# Wifi.net
KiCad netlist of a schematic drawn in Altium Designer
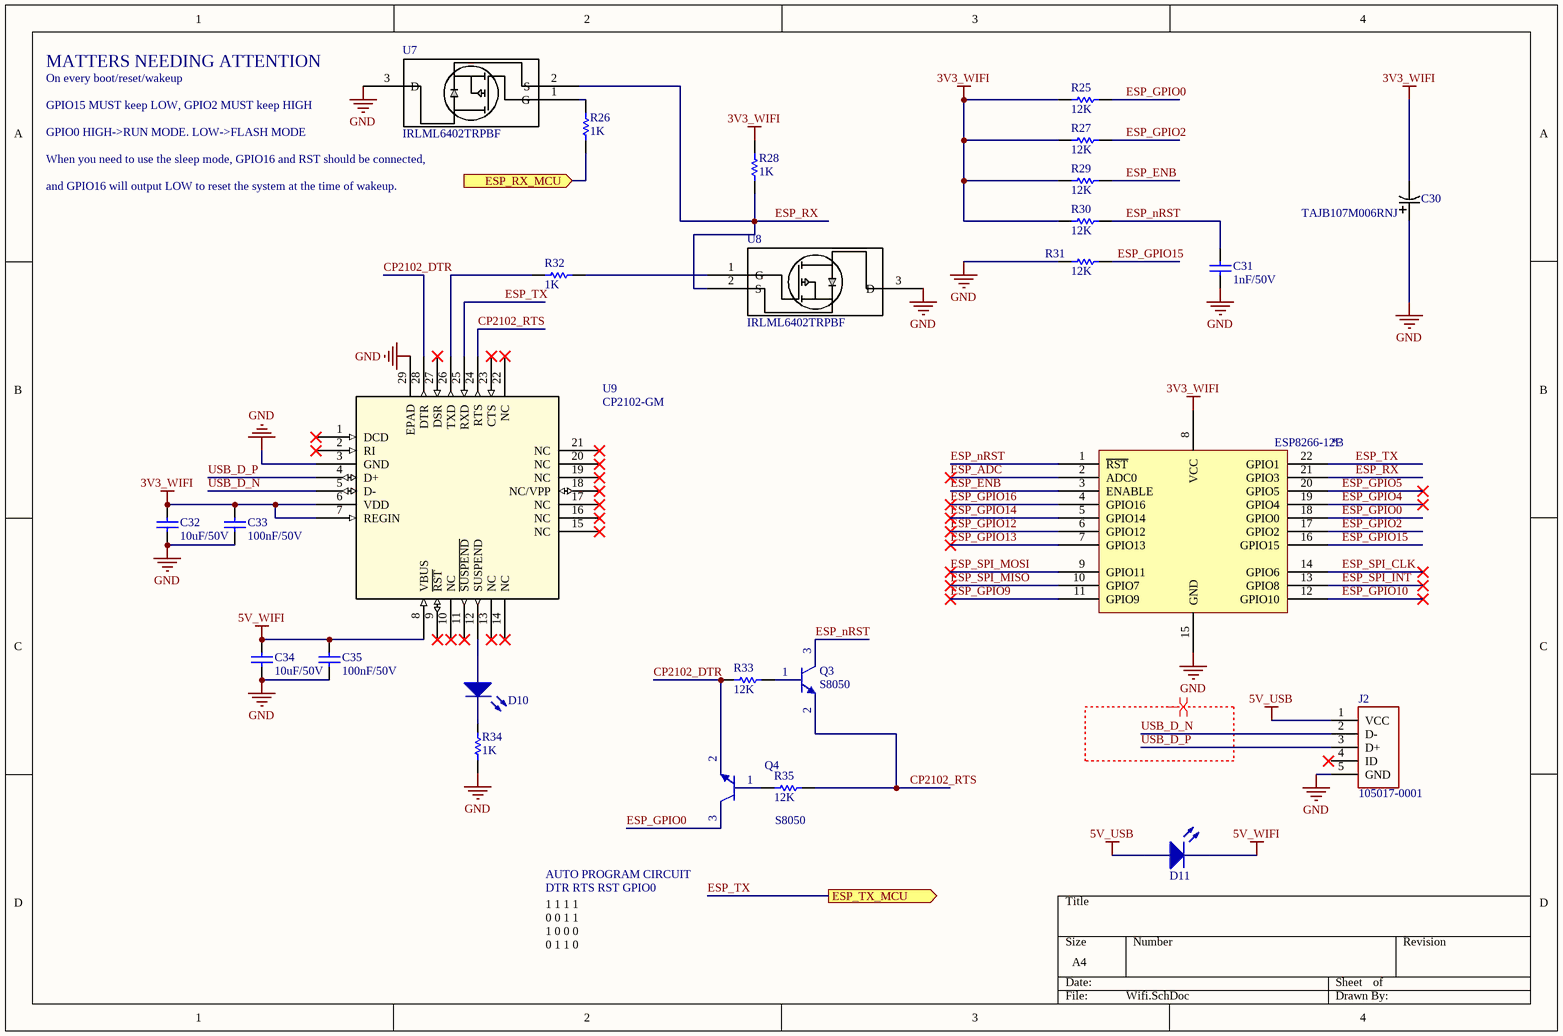
[diagram p0: Wifi.SchDoc]

(export (version "E")
  (design (tool "Eeschema 10.0.6"))
  (components
    (comp (ref "*3")
      (value "ESP8266-12F")
      (footprint "ESP8266")
      (libsource (lib "Schlib1") (part "ESP8266-12F"))
    )
    (comp (ref "C30")
      (value "TAJB107M006RNJ")
      (footprint "TAJB107M006RNJ")
      (fields (field (name "COPYRIGHT") "Copyright (C) 2018 Accelerated Designs. All rights reserved"))
      (libsource (lib "Integrated_Library") (part "TAJB107M006RNJ"))
    )
    (comp (ref "C31")
      (value "1nF/50V")
      (footprint "CAP-SM-0805")
      (description "CAP CER 1000PF 100V X7R 0805")
      (fields
        (field (name "MANUFACTURER") "Johanson Dielectrics Inc.")
        (field (name "MANUFACTURER PART NUMBER") "101X15W102MV4E")
      )
      (libsource (lib "Capacitor") (part "Cap-1nF-50V-0805"))
    )
    (comp (ref "C32")
      (value "10uF/50V")
      (footprint "CAP-SM-0805")
      (description "CAP CER 1000PF 100V X7R 0805")
      (fields
        (field (name "MANUFACTURER") "Johanson Dielectrics Inc.")
        (field (name "MANUFACTURER PART NUMBER") "101X15W102MV4E")
      )
      (libsource (lib "Capacitor") (part "Cap-1nF-50V-0805"))
    )
    (comp (ref "C33")
      (value "100nF/50V")
      (footprint "CAP-SM-0805")
      (description "CAP CER 1000PF 100V X7R 0805")
      (fields
        (field (name "MANUFACTURER") "Johanson Dielectrics Inc.")
        (field (name "MANUFACTURER PART NUMBER") "101X15W102MV4E")
      )
      (libsource (lib "Capacitor") (part "Cap-1nF-50V-0805"))
    )
    (comp (ref "C34")
      (value "10uF/50V")
      (footprint "CAP-SM-0805")
      (description "CAP CER 1000PF 100V X7R 0805")
      (fields
        (field (name "MANUFACTURER") "Johanson Dielectrics Inc.")
        (field (name "MANUFACTURER PART NUMBER") "101X15W102MV4E")
      )
      (libsource (lib "Capacitor") (part "Cap-1nF-50V-0805"))
    )
    (comp (ref "C35")
      (value "100nF/50V")
      (footprint "CAP-SM-0805")
      (description "CAP CER 1000PF 100V X7R 0805")
      (fields
        (field (name "MANUFACTURER") "Johanson Dielectrics Inc.")
        (field (name "MANUFACTURER PART NUMBER") "101X15W102MV4E")
      )
      (libsource (lib "Capacitor") (part "Cap-1nF-50V-0805"))
    )
    (comp (ref "D10") (value "LED") (footprint "LED_0603_Blue") (libsource (lib "PIF_C16_lib") (part "LED")))
    (comp (ref "D11") (value "LED") (footprint "LED_0603_Blue") (libsource (lib "PIF_C16_lib") (part "LED")))
    (comp (ref "J2")
      (value "105017-0001")
      (footprint "CONN_105017-0001")
      (description "No Description Available")
      (fields (field (name "COPYRIGHT") "Copyright (C) 2018 Accelerated Designs. All rights reserved"))
      (libsource (lib "Header-connector") (part "105017-0001"))
    )
    (comp (ref "Q3") (value "S8050") (footprint "SOT23_NEX") (libsource (lib "BJT") (part "S8050")))
    (comp (ref "Q4") (value "S8050") (footprint "SOT23_NEX") (libsource (lib "BJT") (part "S8050")))
    (comp (ref "R25")
      (value "12K")
      (footprint "Resistor:RES-SM-0805")
      (description "RES 0 OHM JUMPER 0805")
      (fields
        (field (name "MANUFACTURER") "Vishay Dale")
        (field (name "MANUFACTURER PART NUMBER") "WSL080500000ZEA9")
      )
      (libsource (lib "Resistor") (part "Res-0-0805"))
    )
    (comp (ref "R26")
      (value "1K")
      (footprint "Resistor:RES-SM-0805")
      (description "RES 470 OHM JUMPER 0805")
      (fields
        (field (name "MANUFACTURER") "YAG6006CT-ND")
        (field (name "MANUFACTURER PART NUMBER") "PE0805FRF7W0R047L")
      )
      (libsource (lib "Resistor") (part "Res-470-0805"))
    )
    (comp (ref "R27")
      (value "12K")
      (footprint "Resistor:RES-SM-0805")
      (description "RES 0 OHM JUMPER 0805")
      (fields
        (field (name "MANUFACTURER") "Vishay Dale")
        (field (name "MANUFACTURER PART NUMBER") "WSL080500000ZEA9")
      )
      (libsource (lib "Resistor") (part "Res-0-0805"))
    )
    (comp (ref "R28")
      (value "1K")
      (footprint "Resistor:RES-SM-0805")
      (description "RES 470 OHM JUMPER 0805")
      (fields
        (field (name "MANUFACTURER") "YAG6006CT-ND")
        (field (name "MANUFACTURER PART NUMBER") "PE0805FRF7W0R047L")
      )
      (libsource (lib "Resistor") (part "Res-470-0805"))
    )
    (comp (ref "R29")
      (value "12K")
      (footprint "Resistor:RES-SM-0805")
      (description "RES 0 OHM JUMPER 0805")
      (fields
        (field (name "MANUFACTURER") "Vishay Dale")
        (field (name "MANUFACTURER PART NUMBER") "WSL080500000ZEA9")
      )
      (libsource (lib "Resistor") (part "Res-0-0805"))
    )
    (comp (ref "R30")
      (value "12K")
      (footprint "Resistor:RES-SM-0805")
      (description "RES 0 OHM JUMPER 0805")
      (fields
        (field (name "MANUFACTURER") "Vishay Dale")
        (field (name "MANUFACTURER PART NUMBER") "WSL080500000ZEA9")
      )
      (libsource (lib "Resistor") (part "Res-0-0805"))
    )
    (comp (ref "R31")
      (value "12K")
      (footprint "Resistor:RES-SM-0805")
      (description "RES 0 OHM JUMPER 0805")
      (fields
        (field (name "MANUFACTURER") "Vishay Dale")
        (field (name "MANUFACTURER PART NUMBER") "WSL080500000ZEA9")
      )
      (libsource (lib "Resistor") (part "Res-0-0805"))
    )
    (comp (ref "R32")
      (value "1K")
      (footprint "Resistor:RES-SM-0805")
      (description "RES 470 OHM JUMPER 0805")
      (fields
        (field (name "MANUFACTURER") "YAG6006CT-ND")
        (field (name "MANUFACTURER PART NUMBER") "PE0805FRF7W0R047L")
      )
      (libsource (lib "Resistor") (part "Res-470-0805"))
    )
    (comp (ref "R33")
      (value "12K")
      (footprint "Resistor:RES-SM-0805")
      (description "RES 0 OHM JUMPER 0805")
      (fields
        (field (name "MANUFACTURER") "Vishay Dale")
        (field (name "MANUFACTURER PART NUMBER") "WSL080500000ZEA9")
      )
      (libsource (lib "Resistor") (part "Res-0-0805"))
    )
    (comp (ref "R34")
      (value "1K")
      (footprint "Resistor:RES-SM-0805")
      (description "RES 470 OHM JUMPER 0805")
      (fields
        (field (name "MANUFACTURER") "YAG6006CT-ND")
        (field (name "MANUFACTURER PART NUMBER") "PE0805FRF7W0R047L")
      )
      (libsource (lib "Resistor") (part "Res-470-0805"))
    )
    (comp (ref "R35")
      (value "12K")
      (footprint "Resistor:RES-SM-0805")
      (description "RES 0 OHM JUMPER 0805")
      (fields
        (field (name "MANUFACTURER") "Vishay Dale")
        (field (name "MANUFACTURER PART NUMBER") "WSL080500000ZEA9")
      )
      (libsource (lib "Resistor") (part "Res-0-0805"))
    )
    (comp (ref "U7")
      (value "IRLML6402TRPBF")
      (footprint "IRLML6402TRPBF")
      (description "No Description Available")
      (fields (field (name "COPYRIGHT") "Copyright (C) 2018 Accelerated Designs. All rights reserved"))
      (libsource (lib "Integrated_Library") (part "IRLML6402TRPBF"))
    )
    (comp (ref "U8")
      (value "IRLML6402TRPBF")
      (footprint "IRLML6402TRPBF")
      (description "No Description Available")
      (fields (field (name "COPYRIGHT") "Copyright (C) 2018 Accelerated Designs. All rights reserved"))
      (libsource (lib "Integrated_Library") (part "IRLML6402TRPBF"))
    )
    (comp (ref "U9")
      (value "CP2102-GM")
      (footprint "cp2102-gm")
      (fields (field (name "COPYRIGHT") "Copyright (C) 2018 Accelerated Designs. All rights reserved"))
      (libsource (lib "Schlib1") (part "CP2102-GM"))
    )
  )
  (nets
    (net (code "1") (name "/CP2102_DTR") (class "Default")
      (node (ref "Q4") (pin "2") (pinfunction "E_2") (pintype "passive"))
      (node (ref "R33") (pin "1") (pinfunction "1_1") (pintype "passive"))
      (node (ref "U9") (pin "28") (pinfunction "DTR_28") (pintype "output"))
    )
    (net (code "2") (name "/CP2102_RTS") (class "Default")
      (node (ref "Q3") (pin "2") (pinfunction "E_2") (pintype "passive"))
      (node (ref "R35") (pin "2") (pinfunction "2_2") (pintype "passive"))
      (node (ref "U9") (pin "24") (pinfunction "RTS_24") (pintype "output"))
    )
    (net (code "3") (name "/ESP_ADC") (class "Default")
      (node (ref "*3") (pin "2") (pinfunction "ADC0_2") (pintype "passive+no_connect"))
    )
    (net (code "4") (name "/ESP_ENB") (class "Default")
      (node (ref "*3") (pin "3") (pinfunction "ENABLE_3") (pintype "passive"))
      (node (ref "R29") (pin "2") (pinfunction "2_2") (pintype "passive"))
    )
    (net (code "5") (name "/ESP_GPIO0") (class "Default")
      (node (ref "*3") (pin "18") (pinfunction "GPIO0_18") (pintype "passive"))
      (node (ref "Q4") (pin "3") (pinfunction "C_3") (pintype "passive"))
      (node (ref "R25") (pin "2") (pinfunction "2_2") (pintype "passive"))
    )
    (net (code "6") (name "/ESP_GPIO2") (class "Default")
      (node (ref "*3") (pin "17") (pinfunction "GPIO2_17") (pintype "passive"))
      (node (ref "R27") (pin "2") (pinfunction "2_2") (pintype "passive"))
    )
    (net (code "7") (name "/ESP_GPIO4") (class "Default")
      (node (ref "*3") (pin "19") (pinfunction "GPIO4_19") (pintype "passive+no_connect"))
    )
    (net (code "8") (name "/ESP_GPIO5") (class "Default")
      (node (ref "*3") (pin "20") (pinfunction "GPIO5_20") (pintype "passive+no_connect"))
    )
    (net (code "9") (name "/ESP_GPIO9") (class "Default")
      (node (ref "*3") (pin "11") (pinfunction "GPIO9_11") (pintype "passive+no_connect"))
    )
    (net (code "10") (name "/ESP_GPIO10") (class "Default")
      (node (ref "*3") (pin "12") (pinfunction "GPIO10_12") (pintype "passive+no_connect"))
    )
    (net (code "11") (name "/ESP_GPIO12") (class "Default")
      (node (ref "*3") (pin "6") (pinfunction "GPIO12_6") (pintype "passive+no_connect"))
    )
    (net (code "12") (name "/ESP_GPIO13") (class "Default")
      (node (ref "*3") (pin "7") (pinfunction "GPIO13_7") (pintype "passive+no_connect"))
    )
    (net (code "13") (name "/ESP_GPIO14") (class "Default")
      (node (ref "*3") (pin "5") (pinfunction "GPIO14_5") (pintype "passive+no_connect"))
    )
    (net (code "14") (name "/ESP_GPIO15") (class "Default")
      (node (ref "*3") (pin "16") (pinfunction "GPIO15_16") (pintype "passive"))
      (node (ref "R31") (pin "2") (pinfunction "2_2") (pintype "passive"))
    )
    (net (code "15") (name "/ESP_GPIO16") (class "Default")
      (node (ref "*3") (pin "4") (pinfunction "GPIO16_4") (pintype "passive+no_connect"))
    )
    (net (code "16") (name "/ESP_RX") (class "Default")
      (node (ref "*3") (pin "21") (pinfunction "GPIO3_21") (pintype "passive"))
      (node (ref "R28") (pin "2") (pinfunction "2_2") (pintype "passive"))
      (node (ref "U7") (pin "2") (pinfunction "S_2") (pintype "passive"))
      (node (ref "U8") (pin "2") (pinfunction "S_2") (pintype "passive"))
    )
    (net (code "17") (name "/ESP_RX_MCU") (class "Default")
      (node (ref "R26") (pin "1") (pinfunction "1_1") (pintype "passive"))
    )
    (net (code "18") (name "/ESP_SPI_CLK") (class "Default")
      (node (ref "*3") (pin "14") (pinfunction "GPIO6_14") (pintype "passive+no_connect"))
    )
    (net (code "19") (name "/ESP_SPI_INT") (class "Default")
      (node (ref "*3") (pin "13") (pinfunction "GPIO8_13") (pintype "passive+no_connect"))
    )
    (net (code "20") (name "/ESP_SPI_MISO") (class "Default")
      (node (ref "*3") (pin "10") (pinfunction "GPIO7_10") (pintype "passive+no_connect"))
    )
    (net (code "21") (name "/ESP_SPI_MOSI") (class "Default")
      (node (ref "*3") (pin "9") (pinfunction "GPIO11_9") (pintype "passive+no_connect"))
    )
    (net (code "22") (name "/ESP_TX") (class "Default")
      (node (ref "*3") (pin "22") (pinfunction "GPIO1_22") (pintype "passive"))
      (node (ref "U9") (pin "25") (pinfunction "RXD_25") (pintype "input"))
    )
    (net (code "23") (name "/ESP_nRST") (class "Default")
      (node (ref "*3") (pin "1") (pinfunction "~{RST}_1") (pintype "passive"))
      (node (ref "C31") (pin "2") (pinfunction "2_2") (pintype "passive"))
      (node (ref "Q3") (pin "3") (pinfunction "C_3") (pintype "passive"))
      (node (ref "R30") (pin "2") (pinfunction "2_2") (pintype "passive"))
    )
    (net (code "24") (name "/USB_D_N") (class "Default")
      (node (ref "J2") (pin "2") (pinfunction "D-_2") (pintype "passive"))
      (node (ref "U9") (pin "5") (pinfunction "D-_5") (pintype "bidirectional"))
    )
    (net (code "25") (name "/USB_D_P") (class "Default")
      (node (ref "J2") (pin "3") (pinfunction "D+_3") (pintype "passive"))
      (node (ref "U9") (pin "4") (pinfunction "D+_4") (pintype "bidirectional"))
    )
    (net (code "26") (name "3V3_WIFI") (class "Default")
      (node (ref "*3") (pin "8") (pinfunction "VCC_8") (pintype "passive"))
      (node (ref "C30") (pin "2") (pinfunction "12_2") (pintype "passive"))
      (node (ref "C32") (pin "2") (pinfunction "2_2") (pintype "passive"))
      (node (ref "C33") (pin "2") (pinfunction "2_2") (pintype "passive"))
      (node (ref "R25") (pin "1") (pinfunction "1_1") (pintype "passive"))
      (node (ref "R27") (pin "1") (pinfunction "1_1") (pintype "passive"))
      (node (ref "R28") (pin "1") (pinfunction "1_1") (pintype "passive"))
      (node (ref "R29") (pin "1") (pinfunction "1_1") (pintype "passive"))
      (node (ref "R30") (pin "1") (pinfunction "1_1") (pintype "passive"))
      (node (ref "U9") (pin "6") (pinfunction "VDD_6") (pintype "power_in"))
      (node (ref "U9") (pin "7") (pinfunction "REGIN_7") (pintype "input"))
    )
    (net (code "27") (name "5V_USB") (class "Default")
      (node (ref "D11") (pin "1") (pinfunction "A_1") (pintype "passive"))
      (node (ref "J2") (pin "1") (pinfunction "VCC_1") (pintype "passive"))
    )
    (net (code "28") (name "5V_WIFI") (class "Default")
      (node (ref "C34") (pin "2") (pinfunction "2_2") (pintype "passive"))
      (node (ref "C35") (pin "2") (pinfunction "2_2") (pintype "passive"))
      (node (ref "D11") (pin "2") (pinfunction "K_2") (pintype "passive"))
      (node (ref "U9") (pin "8") (pinfunction "VBUS_8") (pintype "input"))
    )
    (net (code "29") (name "GND") (class "Default")
      (node (ref "*3") (pin "15") (pinfunction "GND_15") (pintype "passive"))
      (node (ref "C30") (pin "1") (pinfunction "11_1") (pintype "passive"))
      (node (ref "C31") (pin "1") (pinfunction "1_1") (pintype "passive"))
      (node (ref "C32") (pin "1") (pinfunction "1_1") (pintype "passive"))
      (node (ref "C33") (pin "1") (pinfunction "1_1") (pintype "passive"))
      (node (ref "C34") (pin "1") (pinfunction "1_1") (pintype "passive"))
      (node (ref "C35") (pin "1") (pinfunction "1_1") (pintype "passive"))
      (node (ref "J2") (pin "5") (pinfunction "GND_5") (pintype "passive"))
      (node (ref "R31") (pin "1") (pinfunction "1_1") (pintype "passive"))
      (node (ref "R34") (pin "1") (pinfunction "1_1") (pintype "passive"))
      (node (ref "U7") (pin "3") (pinfunction "D_3") (pintype "passive"))
      (node (ref "U8") (pin "3") (pinfunction "D_3") (pintype "passive"))
      (node (ref "U9") (pin "29") (pinfunction "EPAD_29") (pintype "passive"))
      (node (ref "U9") (pin "3") (pinfunction "GND_3") (pintype "power_in"))
    )
    (net (code "30") (name "Net-(D10-A)") (class "Default")
      (node (ref "D10") (pin "1") (pinfunction "A_1") (pintype "passive"))
      (node (ref "U9") (pin "12") (pinfunction "SUSPEND_12") (pintype "output"))
    )
    (net (code "31") (name "Net-(D10-K)") (class "Default")
      (node (ref "D10") (pin "2") (pinfunction "K_2") (pintype "passive"))
      (node (ref "R34") (pin "2") (pinfunction "2_2") (pintype "passive"))
    )
    (net (code "32") (name "Net-(Q3-B)") (class "Default")
      (node (ref "Q3") (pin "1") (pinfunction "B_1") (pintype "passive"))
      (node (ref "R33") (pin "2") (pinfunction "2_2") (pintype "passive"))
    )
    (net (code "33") (name "Net-(Q4-B)") (class "Default")
      (node (ref "Q4") (pin "1") (pinfunction "B_1") (pintype "passive"))
      (node (ref "R35") (pin "1") (pinfunction "1_1") (pintype "passive"))
    )
    (net (code "34") (name "Net-(U7-G)") (class "Default")
      (node (ref "R26") (pin "2") (pinfunction "2_2") (pintype "passive"))
      (node (ref "U7") (pin "1") (pinfunction "G_1") (pintype "passive"))
    )
    (net (code "35") (name "Net-(U8-G)") (class "Default")
      (node (ref "R32") (pin "1") (pinfunction "1_1") (pintype "passive"))
      (node (ref "U8") (pin "1") (pinfunction "G_1") (pintype "passive"))
    )
    (net (code "36") (name "Net-(U9-TXD)") (class "Default")
      (node (ref "R32") (pin "2") (pinfunction "2_2") (pintype "passive"))
      (node (ref "U9") (pin "26") (pinfunction "TXD_26") (pintype "output"))
    )
    (net (code "37") (name "unconnected-(J2-ID-Pad4)") (class "Default")
      (node (ref "J2") (pin "4") (pinfunction "ID_4") (pintype "passive"))
    )
    (net (code "38") (name "unconnected-(U9-CTS-Pad23)") (class "Default")
      (node (ref "U9") (pin "23") (pinfunction "CTS_23") (pintype "input+no_connect"))
    )
    (net (code "39") (name "unconnected-(U9-DCD-Pad1)") (class "Default")
      (node (ref "U9") (pin "1") (pinfunction "DCD_1") (pintype "input+no_connect"))
    )
    (net (code "40") (name "unconnected-(U9-DSR-Pad27)") (class "Default")
      (node (ref "U9") (pin "27") (pinfunction "DSR_27") (pintype "input+no_connect"))
    )
    (net (code "41") (name "unconnected-(U9-NC-Pad10)") (class "Default")
      (node (ref "U9") (pin "10") (pinfunction "NC_10") (pintype "passive+no_connect"))
    )
    (net (code "42") (name "unconnected-(U9-NC-Pad13)") (class "Default")
      (node (ref "U9") (pin "13") (pinfunction "NC_13") (pintype "passive+no_connect"))
    )
    (net (code "43") (name "unconnected-(U9-NC-Pad14)") (class "Default")
      (node (ref "U9") (pin "14") (pinfunction "NC_14") (pintype "passive+no_connect"))
    )
    (net (code "44") (name "unconnected-(U9-NC-Pad15)") (class "Default")
      (node (ref "U9") (pin "15") (pinfunction "NC_15") (pintype "passive+no_connect"))
    )
    (net (code "45") (name "unconnected-(U9-NC-Pad16)") (class "Default")
      (node (ref "U9") (pin "16") (pinfunction "NC_16") (pintype "passive+no_connect"))
    )
    (net (code "46") (name "unconnected-(U9-NC-Pad17)") (class "Default")
      (node (ref "U9") (pin "17") (pinfunction "NC_17") (pintype "passive+no_connect"))
    )
    (net (code "47") (name "unconnected-(U9-NC-Pad19)") (class "Default")
      (node (ref "U9") (pin "19") (pinfunction "NC_19") (pintype "passive+no_connect"))
    )
    (net (code "48") (name "unconnected-(U9-NC-Pad20)") (class "Default")
      (node (ref "U9") (pin "20") (pinfunction "NC_20") (pintype "passive+no_connect"))
    )
    (net (code "49") (name "unconnected-(U9-NC-Pad21)") (class "Default")
      (node (ref "U9") (pin "21") (pinfunction "NC_21") (pintype "passive+no_connect"))
    )
    (net (code "50") (name "unconnected-(U9-NC-Pad22)") (class "Default")
      (node (ref "U9") (pin "22") (pinfunction "NC_22") (pintype "passive+no_connect"))
    )
    (net (code "51") (name "unconnected-(U9-NC{slash}VPP-Pad18)") (class "Default")
      (node (ref "U9") (pin "18") (pinfunction "NC/VPP_18") (pintype "bidirectional+no_connect"))
    )
    (net (code "52") (name "unconnected-(U9-RI-Pad2)") (class "Default")
      (node (ref "U9") (pin "2") (pinfunction "RI_2") (pintype "input+no_connect"))
    )
    (net (code "53") (name "unconnected-(U9-~{RST}-Pad9)") (class "Default")
      (node (ref "U9") (pin "9") (pinfunction "~{RST}_9") (pintype "bidirectional+no_connect"))
    )
    (net (code "54") (name "unconnected-(U9-~{SUSPEND}-Pad11)") (class "Default")
      (node (ref "U9") (pin "11") (pinfunction "~{SUSPEND}_11") (pintype "output+no_connect"))
    )
  )
)
